# Sheet1.net
KiCad netlist of a schematic drawn in Altium Designer
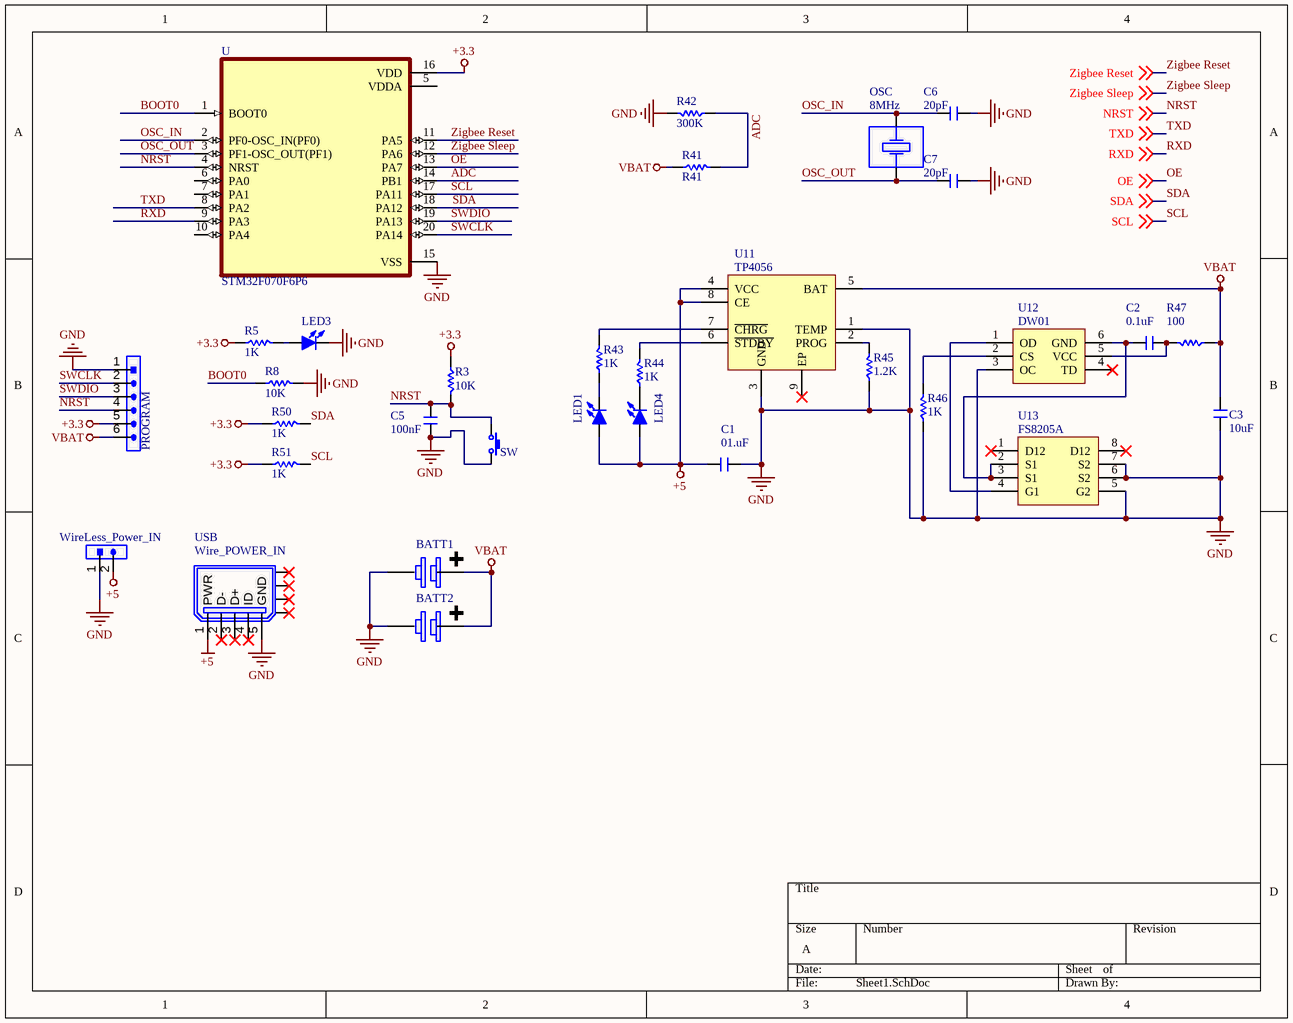
[diagram p0: Sheet1.SchDoc]

(export (version "E")
  (design (tool "Eeschema 10.0.6"))
  (components
    (comp (ref "BATT1")
      (value "Battery 1850")
      (footprint "18650 SINGLE 2")
      (libsource (lib "Battery Holder") (part "Battery 1850"))
    )
    (comp (ref "BATT2")
      (value "Battery 1850")
      (footprint "18650 SINGLE 2")
      (libsource (lib "Battery Holder") (part "Battery 1850"))
    )
    (comp (ref "C1")
      (value "01.uF")
      (footprint "C 0402")
      (description "Non-polar patch capacitor")
      (fields (field (name "版权归属") "源创客"))
      (libsource (lib "Passive (Resistor-Capacitor-Inductor-Veristor-Ferrite)") (part "C"))
    )
    (comp (ref "C2")
      (value "0.1uF")
      (footprint "C 0402")
      (description "Non-polar patch capacitor")
      (fields (field (name "版权归属") "源创客"))
      (libsource (lib "Passive (Resistor-Capacitor-Inductor-Veristor-Ferrite)") (part "C"))
    )
    (comp (ref "C3")
      (value "10uF")
      (footprint "C 0603")
      (description "Non-polar patch capacitor")
      (fields (field (name "版权归属") "源创客"))
      (libsource (lib "Passive (Resistor-Capacitor-Inductor-Veristor-Ferrite)") (part "C"))
    )
    (comp (ref "C5")
      (value "100nF")
      (footprint "C 0805")
      (description "Non-polar patch capacitor")
      (fields (field (name "版权归属") "源创客"))
      (libsource (lib "Passive (Resistor-Capacitor-Inductor-Veristor-Ferrite)") (part "C"))
    )
    (comp (ref "C6")
      (value "20pF")
      (footprint "C 0805")
      (description "Non-polar patch capacitor")
      (fields (field (name "版权归属") "源创客"))
      (libsource (lib "Passive (Resistor-Capacitor-Inductor-Veristor-Ferrite)") (part "C"))
    )
    (comp (ref "C7")
      (value "20pF")
      (footprint "C 0805")
      (description "Non-polar patch capacitor")
      (fields (field (name "版权归属") "源创客"))
      (libsource (lib "Passive (Resistor-Capacitor-Inductor-Veristor-Ferrite)") (part "C"))
    )
    (comp (ref "LED1")
      (value "LED-SMD")
      (footprint "LED 0805R")
      (description "Patch LED")
      (fields (field (name "版权归属") "源创客"))
      (libsource (lib "LED") (part "LED-SMD"))
    )
    (comp (ref "LED3")
      (value "LED-SMD")
      (footprint "LED 0805R")
      (description "Patch LED")
      (fields (field (name "版权归属") "源创客"))
      (libsource (lib "LED") (part "LED-SMD"))
    )
    (comp (ref "LED4")
      (value "LED-SMD")
      (footprint "LED 0805G")
      (description "Patch LED")
      (fields (field (name "版权归属") "源创客"))
      (libsource (lib "LED") (part "LED-SMD"))
    )
    (comp (ref "OSC")
      (value "8MHz")
      (footprint "XTAL-HC49S-THD")
      (description "2-Pin crystal")
      (fields (field (name "版权归属") "源创客"))
      (libsource (lib "Crystal Oscillator") (part "XTAL-2"))
    )
    (comp (ref "PROGRAM")
      (value "HDR-1X6")
      (footprint "HDR-1X6")
      (description "6P Connector")
      (fields (field (name "版权归属") "源创客"))
      (libsource (lib "Connectors") (part "Header 6"))
    )
    (comp (ref "R3")
      (value "10K")
      (footprint "R 0805")
      (description "Chip resistor")
      (fields (field (name "版权归属") "源创客"))
      (libsource (lib "Passive (Resistor-Capacitor-Inductor-Veristor-Ferrite)") (part "R"))
    )
    (comp (ref "R5")
      (value "1K")
      (footprint "R 0805")
      (description "Chip resistor")
      (fields (field (name "版权归属") "源创客"))
      (libsource (lib "Passive (Resistor-Capacitor-Inductor-Veristor-Ferrite)") (part "R"))
    )
    (comp (ref "R8")
      (value "10K")
      (footprint "R 0805")
      (description "Chip resistor")
      (fields (field (name "版权归属") "源创客"))
      (libsource (lib "Passive (Resistor-Capacitor-Inductor-Veristor-Ferrite)") (part "R"))
    )
    (comp (ref "R41")
      (value "R41")
      (footprint "R 0805")
      (description "Chip resistor")
      (fields (field (name "版权归属") "源创客"))
      (libsource (lib "Passive (Resistor-Capacitor-Inductor-Veristor-Ferrite)") (part "R"))
    )
    (comp (ref "R42")
      (value "300K")
      (footprint "R 0805")
      (description "Chip resistor")
      (fields (field (name "版权归属") "源创客"))
      (libsource (lib "Passive (Resistor-Capacitor-Inductor-Veristor-Ferrite)") (part "R"))
    )
    (comp (ref "R43")
      (value "1K")
      (footprint "R 0402")
      (description "Chip resistor")
      (fields (field (name "版权归属") "源创客"))
      (libsource (lib "Passive (Resistor-Capacitor-Inductor-Veristor-Ferrite)") (part "R"))
    )
    (comp (ref "R44")
      (value "1K")
      (footprint "R 0402")
      (description "Chip resistor")
      (fields (field (name "版权归属") "源创客"))
      (libsource (lib "Passive (Resistor-Capacitor-Inductor-Veristor-Ferrite)") (part "R"))
    )
    (comp (ref "R45")
      (value "1.2K")
      (footprint "R 0402")
      (description "Chip resistor")
      (fields (field (name "版权归属") "源创客"))
      (libsource (lib "Passive (Resistor-Capacitor-Inductor-Veristor-Ferrite)") (part "R"))
    )
    (comp (ref "R46")
      (value "1K")
      (footprint "R 0402")
      (description "Chip resistor")
      (fields (field (name "版权归属") "源创客"))
      (libsource (lib "Passive (Resistor-Capacitor-Inductor-Veristor-Ferrite)") (part "R"))
    )
    (comp (ref "R47")
      (value "100")
      (footprint "R 0402")
      (description "Chip resistor")
      (fields (field (name "版权归属") "源创客"))
      (libsource (lib "Passive (Resistor-Capacitor-Inductor-Veristor-Ferrite)") (part "R"))
    )
    (comp (ref "R50")
      (value "1K")
      (footprint "R 0805")
      (description "Chip resistor")
      (fields (field (name "版权归属") "源创客"))
      (libsource (lib "Passive (Resistor-Capacitor-Inductor-Veristor-Ferrite)") (part "R"))
    )
    (comp (ref "R51")
      (value "1K")
      (footprint "R 0805")
      (description "Chip resistor")
      (fields (field (name "版权归属") "源创客"))
      (libsource (lib "Passive (Resistor-Capacitor-Inductor-Veristor-Ferrite)") (part "R"))
    )
    (comp (ref "SW")
      (value "3x6x5")
      (footprint "TSW SMD-3*6*2.5")
      (description "3x6 tact switch")
      (fields (field (name "版权归属") "源创客"))
      (libsource (lib "Button") (part "TSW 3x6"))
    )
    (comp (ref "U")
      (value "STM32F070F6P6")
      (footprint "SOP65P640X120-20N")
      (description "ARMÂ® CortexÂ®-M0 STM32F0 Microcontroller IC 32-Bit 48MHz 32KB _32K x 8_ FLASH 20-TSSOP")
      (fields (field (name "MF") "STMicroelectronics") (field (name "DIGI-KEY_PART_NUMBER") "497-17354-2-ND"))
      (libsource (lib "STM32F070F6P6") (part "STM32F070F6P6"))
    )
    (comp (ref "U11")
      (value "TP4056")
      (footprint "SOP8_M-EP")
      (description "Lithium battery charge management")
      (fields (field (name "版权归属") "源创客"))
      (libsource (lib "Integrated Circuit") (part "TP4056"))
    )
    (comp (ref "U12")
      (value "DW01")
      (footprint "SOT23-6M")
      (description "Lithium battery overcurrent protection IC")
      (fields (field (name "版权归属") "源创客"))
      (libsource (lib "Integrated Circuit") (part "DW01"))
    )
    (comp (ref "U13")
      (value "FS8205A")
      (footprint "SSOP8_L")
      (description "Dual N-Channel Enhancement Mode Power MOSFET")
      (libsource (lib "Integrated Circuit") (part "FS8205A"))
    )
    (comp (ref "USB")
      (value "Wire_POWER_IN")
      (footprint "USB-micro_B")
      (description "Micro & Mini USB female")
      (fields (field (name "版权归属") "源创客"))
      (libsource (lib "IO (Power-USB-Serial-VGA-RJ-Audio-Buzzer)") (part "USB-5P"))
    )
    (comp (ref "WireLess_Power_IN")
      (value "HDR-1X2")
      (footprint "XH2.54-2P")
      (description "2P Connector")
      (fields (field (name "版权归属") "源创客"))
      (libsource (lib "Connectors") (part "Header 2"))
    )
  )
  (nets
    (net (code "1") (name "+3.3") (class "Default")
      (node (ref "PROGRAM") (pin "5") (pintype "passive"))
      (node (ref "R3") (pin "1") (pinfunction "1_1") (pintype "passive"))
      (node (ref "R5") (pin "1") (pinfunction "1_1") (pintype "passive"))
      (node (ref "R50") (pin "1") (pinfunction "1_1") (pintype "passive"))
      (node (ref "R51") (pin "1") (pinfunction "1_1") (pintype "passive"))
      (node (ref "U") (pin "16") (pinfunction "VDD_16") (pintype "power_in"))
    )
    (net (code "2") (name "+5") (class "Default")
      (node (ref "C1") (pin "2") (pinfunction "2_2") (pintype "passive"))
      (node (ref "LED1") (pin "1") (pinfunction "A_1") (pintype "passive"))
      (node (ref "LED4") (pin "1") (pinfunction "A_1") (pintype "passive"))
      (node (ref "U11") (pin "4") (pinfunction "VCC_4") (pintype "passive"))
      (node (ref "U11") (pin "8") (pinfunction "CE_8") (pintype "passive"))
      (node (ref "USB") (pin "1") (pinfunction "PWR_1") (pintype "power_in"))
      (node (ref "WireLess_Power_IN") (pin "2") (pintype "passive"))
    )
    (net (code "3") (name "/ADC") (class "Default")
      (node (ref "R41") (pin "2") (pinfunction "2_2") (pintype "passive"))
      (node (ref "R42") (pin "1") (pinfunction "1_1") (pintype "passive"))
      (node (ref "U") (pin "14") (pinfunction "PB1_14") (pintype "bidirectional"))
    )
    (net (code "4") (name "/BOOT0") (class "Default")
      (node (ref "R8") (pin "1") (pinfunction "1_1") (pintype "passive"))
      (node (ref "U") (pin "1") (pinfunction "BOOT0_1") (pintype "input"))
    )
    (net (code "5") (name "/OSC_IN") (class "Default")
      (node (ref "C6") (pin "2") (pinfunction "2_2") (pintype "passive"))
      (node (ref "OSC") (pin "2") (pinfunction "3_2") (pintype "passive"))
      (node (ref "U") (pin "2") (pinfunction "PF0-OSC_IN(PF0)_2") (pintype "bidirectional"))
    )
    (net (code "6") (name "/OSC_OUT") (class "Default")
      (node (ref "C7") (pin "2") (pinfunction "2_2") (pintype "passive"))
      (node (ref "OSC") (pin "1") (pinfunction "1_1") (pintype "passive"))
      (node (ref "U") (pin "3") (pinfunction "PF1-OSC_OUT(PF1)_3") (pintype "bidirectional"))
    )
    (net (code "7") (name "/SWCLK") (class "Default")
      (node (ref "PROGRAM") (pin "2") (pintype "passive"))
      (node (ref "U") (pin "20") (pinfunction "PA14_20") (pintype "bidirectional"))
    )
    (net (code "8") (name "/SWDIO") (class "Default")
      (node (ref "PROGRAM") (pin "3") (pintype "passive"))
      (node (ref "U") (pin "19") (pinfunction "PA13_19") (pintype "bidirectional"))
    )
    (net (code "9") (name "GND") (class "Default")
      (node (ref "BATT1") (pin "2") (pinfunction "-_2") (pintype "passive"))
      (node (ref "BATT2") (pin "2") (pinfunction "-_2") (pintype "passive"))
      (node (ref "C1") (pin "1") (pinfunction "1_1") (pintype "passive"))
      (node (ref "C3") (pin "1") (pinfunction "1_1") (pintype "passive"))
      (node (ref "C5") (pin "1") (pinfunction "1_1") (pintype "passive"))
      (node (ref "C6") (pin "1") (pinfunction "1_1") (pintype "passive"))
      (node (ref "C7") (pin "1") (pinfunction "1_1") (pintype "passive"))
      (node (ref "LED3") (pin "2") (pinfunction "K_2") (pintype "passive"))
      (node (ref "PROGRAM") (pin "1") (pintype "passive"))
      (node (ref "R42") (pin "2") (pinfunction "2_2") (pintype "passive"))
      (node (ref "R45") (pin "1") (pinfunction "1_1") (pintype "passive"))
      (node (ref "R46") (pin "1") (pinfunction "1_1") (pintype "passive"))
      (node (ref "R8") (pin "2") (pinfunction "2_2") (pintype "passive"))
      (node (ref "SW") (pin "2") (pinfunction "2_2") (pintype "passive"))
      (node (ref "U") (pin "15") (pinfunction "VSS_15") (pintype "power_in"))
      (node (ref "U11") (pin "1") (pinfunction "TEMP_1") (pintype "passive"))
      (node (ref "U11") (pin "3") (pinfunction "GND_3") (pintype "passive"))
      (node (ref "U12") (pin "3") (pinfunction "OC_3") (pintype "passive"))
      (node (ref "U13") (pin "5") (pinfunction "G2_5") (pintype "passive"))
      (node (ref "U13") (pin "6") (pinfunction "S2_6") (pintype "passive"))
      (node (ref "U13") (pin "7") (pinfunction "S2_7") (pintype "passive"))
      (node (ref "USB") (pin "5") (pinfunction "GND_5") (pintype "power_in"))
      (node (ref "WireLess_Power_IN") (pin "1") (pintype "passive"))
    )
    (net (code "10") (name "NRST") (class "Default")
      (node (ref "C5") (pin "2") (pinfunction "2_2") (pintype "passive"))
      (node (ref "PROGRAM") (pin "4") (pintype "passive"))
      (node (ref "R3") (pin "2") (pinfunction "2_2") (pintype "passive"))
      (node (ref "SW") (pin "1") (pinfunction "1_1") (pintype "passive"))
      (node (ref "U") (pin "4") (pinfunction "NRST_4") (pintype "bidirectional"))
    )
    (net (code "11") (name "Net-(LED1-K)") (class "Default")
      (node (ref "LED1") (pin "2") (pinfunction "K_2") (pintype "passive"))
      (node (ref "R43") (pin "1") (pinfunction "1_1") (pintype "passive"))
    )
    (net (code "12") (name "Net-(LED3-A)") (class "Default")
      (node (ref "LED3") (pin "1") (pinfunction "A_1") (pintype "passive"))
      (node (ref "R5") (pin "2") (pinfunction "2_2") (pintype "passive"))
    )
    (net (code "13") (name "Net-(LED4-K)") (class "Default")
      (node (ref "LED4") (pin "2") (pinfunction "K_2") (pintype "passive"))
      (node (ref "R44") (pin "1") (pinfunction "1_1") (pintype "passive"))
    )
    (net (code "14") (name "Net-(U11-PROG)") (class "Default")
      (node (ref "R45") (pin "2") (pinfunction "2_2") (pintype "passive"))
      (node (ref "U11") (pin "2") (pinfunction "PROG_2") (pintype "passive"))
    )
    (net (code "15") (name "Net-(U11-~{CHRG})") (class "Default")
      (node (ref "R43") (pin "2") (pinfunction "2_2") (pintype "passive"))
      (node (ref "U11") (pin "7") (pinfunction "~{CHRG}_7") (pintype "passive"))
    )
    (net (code "16") (name "Net-(U11-~{STDBY})") (class "Default")
      (node (ref "R44") (pin "2") (pinfunction "2_2") (pintype "passive"))
      (node (ref "U11") (pin "6") (pinfunction "~{STDBY}_6") (pintype "passive"))
    )
    (net (code "17") (name "Net-(U12-CS)") (class "Default")
      (node (ref "R46") (pin "2") (pinfunction "2_2") (pintype "passive"))
      (node (ref "U12") (pin "2") (pinfunction "CS_2") (pintype "passive"))
    )
    (net (code "18") (name "Net-(U12-GND)") (class "Default")
      (node (ref "C2") (pin "1") (pinfunction "1_1") (pintype "passive"))
      (node (ref "U12") (pin "6") (pinfunction "GND_6") (pintype "passive"))
      (node (ref "U13") (pin "2") (pinfunction "S1_2") (pintype "passive"))
      (node (ref "U13") (pin "3") (pinfunction "S1_3") (pintype "passive"))
    )
    (net (code "19") (name "Net-(U12-OD)") (class "Default")
      (node (ref "U12") (pin "1") (pinfunction "OD_1") (pintype "passive"))
      (node (ref "U13") (pin "4") (pinfunction "G1_4") (pintype "passive"))
    )
    (net (code "20") (name "Net-(U12-VCC)") (class "Default")
      (node (ref "C2") (pin "2") (pinfunction "2_2") (pintype "passive"))
      (node (ref "R47") (pin "2") (pinfunction "2_2") (pintype "passive"))
      (node (ref "U12") (pin "5") (pinfunction "VCC_5") (pintype "passive"))
    )
    (net (code "21") (name "OE") (class "Default")
      (node (ref "U") (pin "13") (pinfunction "PA7_13") (pintype "bidirectional"))
    )
    (net (code "22") (name "RXD") (class "Default")
      (node (ref "U") (pin "9") (pinfunction "PA3_9") (pintype "bidirectional"))
    )
    (net (code "23") (name "SCL") (class "Default")
      (node (ref "R51") (pin "2") (pinfunction "2_2") (pintype "passive"))
      (node (ref "U") (pin "17") (pinfunction "PA11_17") (pintype "bidirectional"))
    )
    (net (code "24") (name "SDA") (class "Default")
      (node (ref "R50") (pin "2") (pinfunction "2_2") (pintype "passive"))
      (node (ref "U") (pin "18") (pinfunction "PA12_18") (pintype "bidirectional"))
    )
    (net (code "25") (name "TXD") (class "Default")
      (node (ref "U") (pin "8") (pinfunction "PA2_8") (pintype "bidirectional"))
    )
    (net (code "26") (name "VBAT") (class "Default")
      (node (ref "BATT1") (pin "1") (pinfunction "+_1") (pintype "passive"))
      (node (ref "BATT2") (pin "1") (pinfunction "+_1") (pintype "passive"))
      (node (ref "C3") (pin "2") (pinfunction "2_2") (pintype "passive"))
      (node (ref "PROGRAM") (pin "6") (pintype "passive"))
      (node (ref "R41") (pin "1") (pinfunction "1_1") (pintype "passive"))
      (node (ref "R47") (pin "1") (pinfunction "1_1") (pintype "passive"))
      (node (ref "U11") (pin "5") (pinfunction "BAT_5") (pintype "passive"))
    )
    (net (code "27") (name "Zigbee Reset") (class "Default")
      (node (ref "U") (pin "11") (pinfunction "PA5_11") (pintype "bidirectional"))
    )
    (net (code "28") (name "Zigbee Sleep") (class "Default")
      (node (ref "U") (pin "12") (pinfunction "PA6_12") (pintype "bidirectional"))
    )
    (net (code "29") (name "unconnected-(U-PA0-Pad6)") (class "Default")
      (node (ref "U") (pin "6") (pinfunction "PA0_6") (pintype "bidirectional"))
    )
    (net (code "30") (name "unconnected-(U-PA1-Pad7)") (class "Default")
      (node (ref "U") (pin "7") (pinfunction "PA1_7") (pintype "bidirectional"))
    )
    (net (code "31") (name "unconnected-(U-PA4-Pad10)") (class "Default")
      (node (ref "U") (pin "10") (pinfunction "PA4_10") (pintype "bidirectional"))
    )
    (net (code "32") (name "unconnected-(U-VDDA-Pad5)") (class "Default")
      (node (ref "U") (pin "5") (pinfunction "VDDA_5") (pintype "power_in"))
    )
    (net (code "33") (name "unconnected-(U11-EP-Pad9)") (class "Default")
      (node (ref "U11") (pin "9") (pinfunction "EP_9") (pintype "passive+no_connect"))
    )
    (net (code "34") (name "unconnected-(U12-TD-Pad4)") (class "Default")
      (node (ref "U12") (pin "4") (pinfunction "TD_4") (pintype "passive+no_connect"))
    )
    (net (code "35") (name "unconnected-(U13-D12-Pad1)") (class "Default")
      (node (ref "U13") (pin "1") (pinfunction "D12_1") (pintype "passive+no_connect"))
    )
    (net (code "36") (name "unconnected-(U13-D12-Pad8)") (class "Default")
      (node (ref "U13") (pin "8") (pinfunction "D12_8") (pintype "passive+no_connect"))
    )
    (net (code "37") (name "unconnected-(USB-D+-Pad3)") (class "Default")
      (node (ref "USB") (pin "3") (pinfunction "D+_3") (pintype "tri_state+no_connect"))
    )
    (net (code "38") (name "unconnected-(USB-D--Pad2)") (class "Default")
      (node (ref "USB") (pin "2") (pinfunction "D-_2") (pintype "tri_state+no_connect"))
    )
    (net (code "39") (name "unconnected-(USB-ID-Pad4)") (class "Default")
      (node (ref "USB") (pin "4") (pinfunction "ID_4") (pintype "passive+no_connect"))
    )
    (net (code "40") (name "unconnected-(USB-SHIELD-Pad5)") (class "Default")
      (node (ref "USB") (pin "5") (pinfunction "SHIELD_5") (pintype "passive+no_connect"))
    )
    (net (code "41") (name "unconnected-(USB-SHIELD-Pad5)_1") (class "Default")
      (node (ref "USB") (pin "5") (pinfunction "SHIELD_5") (pintype "passive+no_connect"))
    )
    (net (code "42") (name "unconnected-(USB-SHIELD-Pad5)_2") (class "Default")
      (node (ref "USB") (pin "5") (pinfunction "SHIELD_5") (pintype "passive+no_connect"))
    )
    (net (code "43") (name "unconnected-(USB-SHIELD-Pad5)_3") (class "Default")
      (node (ref "USB") (pin "5") (pinfunction "SHIELD_5") (pintype "passive+no_connect"))
    )
  )
)
